# galvo-schematic.net
KiCad netlist of a schematic drawn in EAGLE
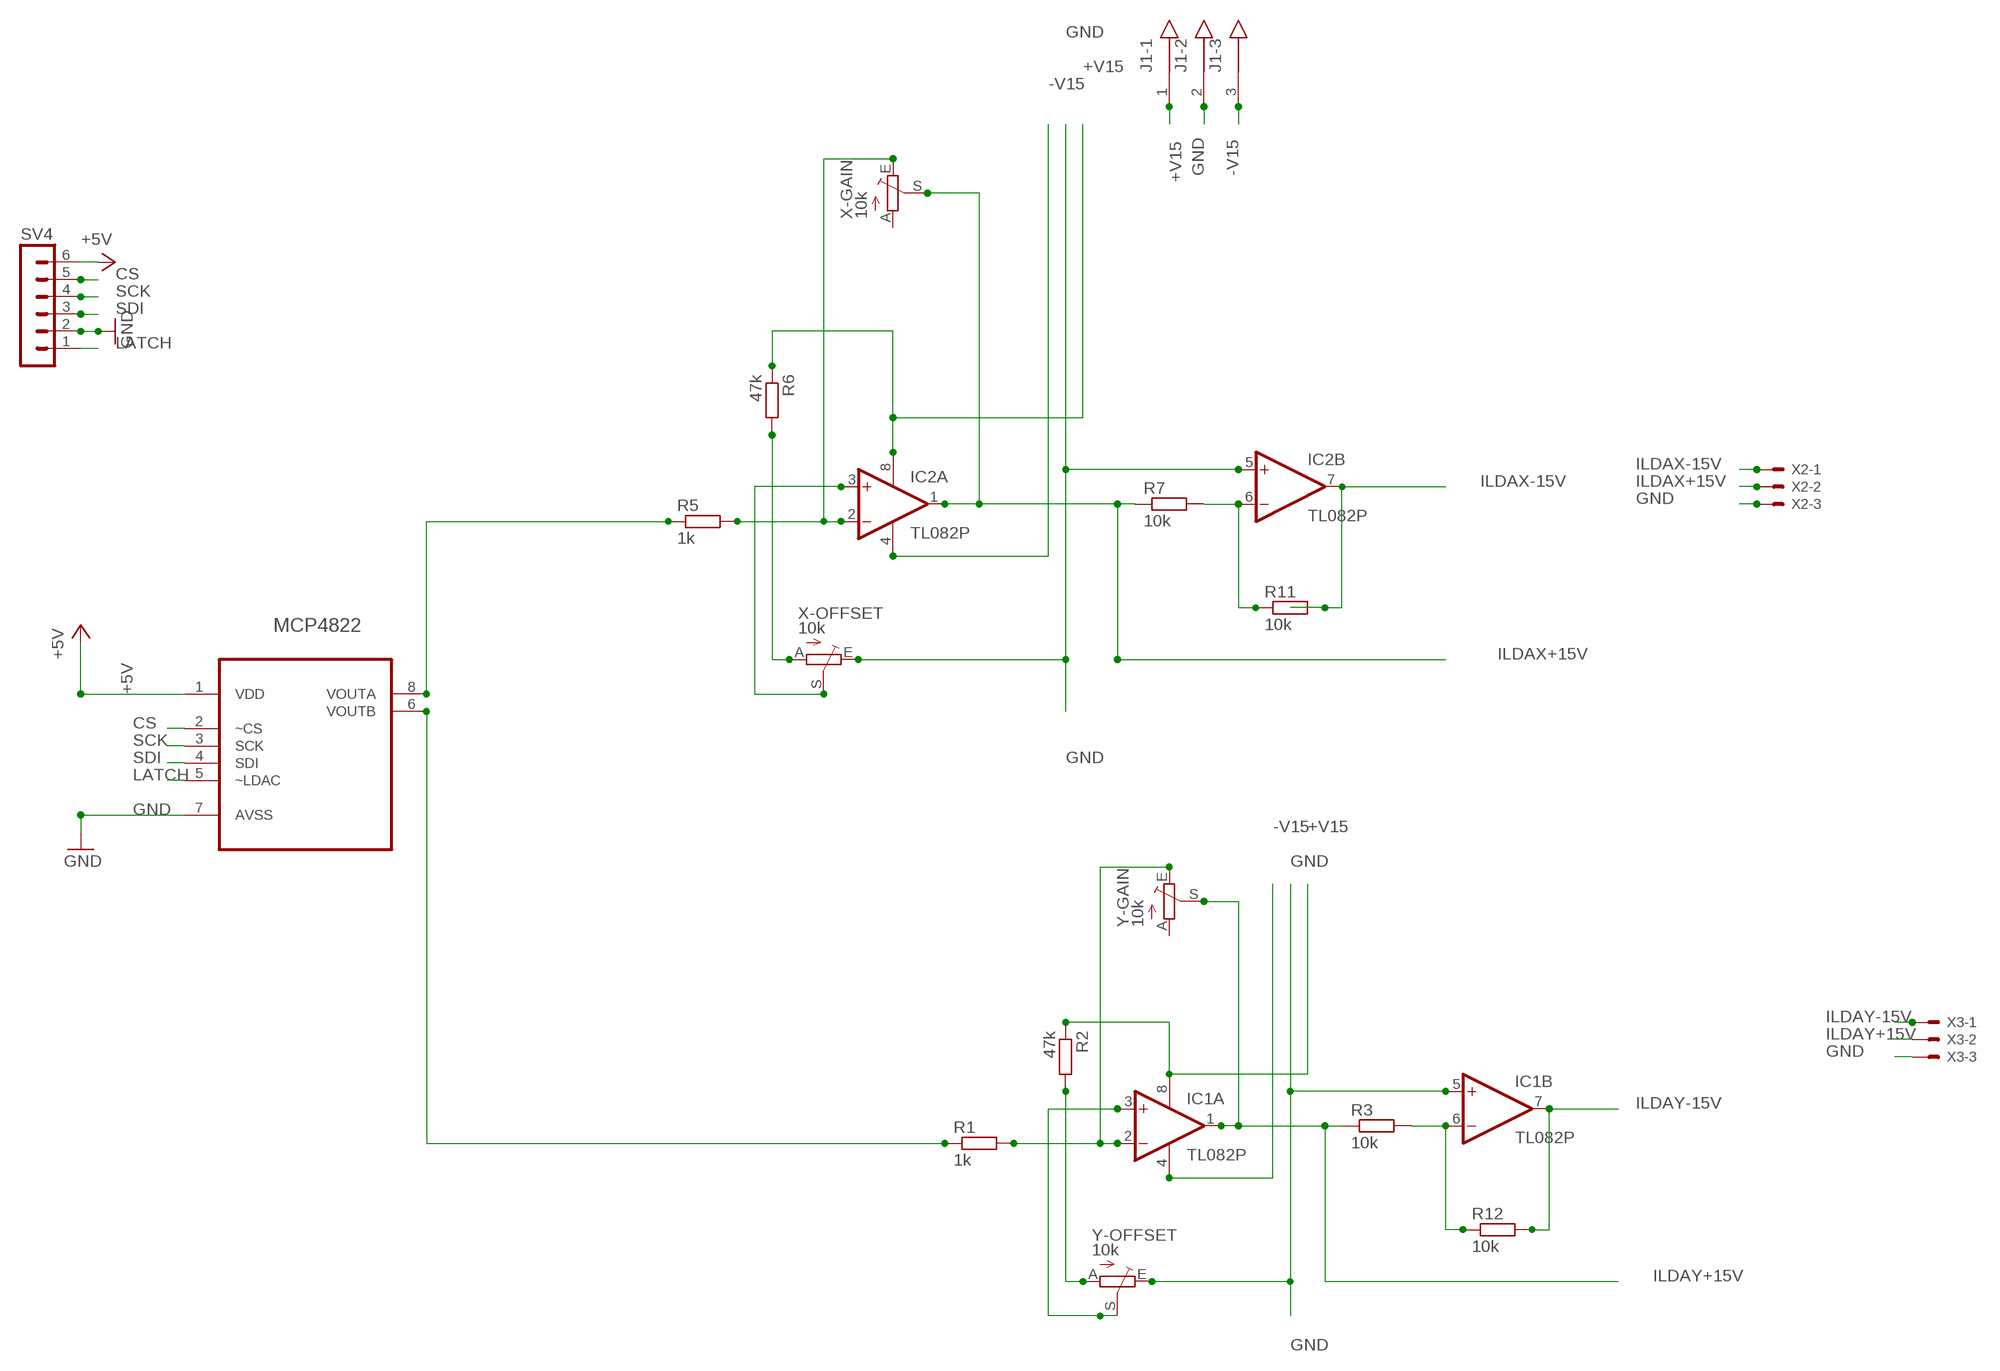
[diagram p0: schematic, sheet 1]

(export (version "E")
  (design (tool "Eeschema 10.0.6"))
  (components
    (comp (ref "IC1")
      (value "TL082P")
      (footprint "eagle-import:DIL08")
      (libsource (lib "eagle-import") (part "TL082P"))
    )
    (comp (ref "IC2")
      (value "TL082P")
      (footprint "eagle-import:DIL08")
      (libsource (lib "eagle-import") (part "TL082P"))
    )
    (comp (ref "J1")
      (value "0022272031")
      (footprint "eagle-import:KK6410-2031_3-PIN")
      (fields (field (name "MANUFACTURER") "Molex Inc"))
      (libsource (lib "eagle-import") (part "0022272031"))
    )
    (comp (ref "MCP4822")
      (value "MCP4822-E/P")
      (footprint "eagle-import:DIP254P762X432-8")
      (libsource (lib "eagle-import") (part "MCP4822-E/P"))
    )
    (comp (ref "R1")
      (value "1k")
      (footprint "eagle-import:0207_10")
      (libsource (lib "eagle-import") (part "R-EU_0207/10"))
    )
    (comp (ref "R2")
      (value "47k")
      (footprint "eagle-import:0207_10")
      (libsource (lib "eagle-import") (part "R-EU_0207/10"))
    )
    (comp (ref "R3")
      (value "10k")
      (footprint "eagle-import:0207_10")
      (libsource (lib "eagle-import") (part "R-EU_0207/10"))
    )
    (comp (ref "R5")
      (value "1k")
      (footprint "eagle-import:0207_10")
      (libsource (lib "eagle-import") (part "R-EU_0207/10"))
    )
    (comp (ref "R6")
      (value "47k")
      (footprint "eagle-import:0207_10")
      (libsource (lib "eagle-import") (part "R-EU_0207/10"))
    )
    (comp (ref "R7")
      (value "10k")
      (footprint "eagle-import:0207_10")
      (libsource (lib "eagle-import") (part "R-EU_0207/10"))
    )
    (comp (ref "R11")
      (value "10k")
      (footprint "eagle-import:0207_10")
      (libsource (lib "eagle-import") (part "R-EU_0207/10"))
    )
    (comp (ref "R12")
      (value "10k")
      (footprint "eagle-import:0207_10")
      (libsource (lib "eagle-import") (part "R-EU_0207/10"))
    )
    (comp (ref "SV4")
      (value "MA06-1")
      (footprint "eagle-import:MA06-1")
      (libsource (lib "eagle-import") (part "MA06-1"))
    )
    (comp (ref "X-GAIN")
      (value "10k")
      (footprint "eagle-import:B25P")
      (libsource (lib "eagle-import") (part "TRIM_EU-B25P"))
    )
    (comp (ref "X-OFFSET")
      (value "10k")
      (footprint "eagle-import:B25P")
      (libsource (lib "eagle-import") (part "TRIM_EU-B25P"))
    )
    (comp (ref "X2")
      (value "JST-XH-03-PIN-ROUND-PAD")
      (footprint "eagle-import:JST-XH-03-PACKAGE-ROUND-PAD")
      (libsource (lib "eagle-import") (part "JST-XH-03-PIN-ROUND-PAD"))
    )
    (comp (ref "X3")
      (value "JST-XH-03-PIN-ROUND-PAD")
      (footprint "eagle-import:JST-XH-03-PACKAGE-ROUND-PAD")
      (libsource (lib "eagle-import") (part "JST-XH-03-PIN-ROUND-PAD"))
    )
    (comp (ref "Y-GAIN")
      (value "10k")
      (footprint "eagle-import:B25P")
      (libsource (lib "eagle-import") (part "TRIM_EU-B25P"))
    )
    (comp (ref "Y-OFFSET")
      (value "10k")
      (footprint "eagle-import:B25P")
      (libsource (lib "eagle-import") (part "TRIM_EU-B25P"))
    )
  )
  (nets
    (net (code "1") (name "+5V") (class "Default")
      (node (ref "MCP4822") (pin "1") (pinfunction "VDD_1") (pintype "power_in"))
      (node (ref "SV4") (pin "6") (pinfunction "6_6") (pintype "passive"))
    )
    (net (code "2") (name "/+V15") (class "Default")
      (node (ref "IC1") (pin "8") (pinfunction "V+_8") (pintype "power_in"))
      (node (ref "IC2") (pin "8") (pinfunction "V+_8") (pintype "power_in"))
      (node (ref "J1") (pin "1") (pinfunction "P$1_1") (pintype "bidirectional"))
      (node (ref "R2") (pin "1") (pinfunction "1_1") (pintype "passive"))
      (node (ref "R6") (pin "1") (pinfunction "1_1") (pintype "passive"))
    )
    (net (code "3") (name "/-V15") (class "Default")
      (node (ref "IC1") (pin "4") (pinfunction "V-_4") (pintype "power_in"))
      (node (ref "IC2") (pin "4") (pinfunction "V-_4") (pintype "power_in"))
      (node (ref "J1") (pin "3") (pinfunction "P$1_3") (pintype "bidirectional"))
    )
    (net (code "4") (name "/CS") (class "Default")
      (node (ref "MCP4822") (pin "2") (pinfunction "~{CS}_2") (pintype "input"))
      (node (ref "SV4") (pin "5") (pinfunction "5_5") (pintype "passive"))
    )
    (net (code "5") (name "/ILDAX+15V") (class "Default")
      (node (ref "IC2") (pin "1") (pinfunction "OUT_1") (pintype "output"))
      (node (ref "R7") (pin "1") (pinfunction "1_1") (pintype "passive"))
      (node (ref "X-GAIN") (pin "S") (pinfunction "S_S") (pintype "passive"))
      (node (ref "X2") (pin "2") (pinfunction "S_2") (pintype "passive"))
    )
    (net (code "6") (name "/ILDAX-15V") (class "Default")
      (node (ref "IC2") (pin "7") (pinfunction "OUT_7") (pintype "output"))
      (node (ref "R11") (pin "2") (pinfunction "2_2") (pintype "passive"))
      (node (ref "X2") (pin "1") (pinfunction "S_1") (pintype "passive"))
    )
    (net (code "7") (name "/ILDAY+15V") (class "Default")
      (node (ref "IC1") (pin "1") (pinfunction "OUT_1") (pintype "output"))
      (node (ref "R3") (pin "1") (pinfunction "1_1") (pintype "passive"))
      (node (ref "X3") (pin "2") (pinfunction "S_2") (pintype "passive"))
      (node (ref "Y-GAIN") (pin "S") (pinfunction "S_S") (pintype "passive"))
    )
    (net (code "8") (name "/ILDAY-15V") (class "Default")
      (node (ref "IC1") (pin "7") (pinfunction "OUT_7") (pintype "output"))
      (node (ref "R12") (pin "2") (pinfunction "2_2") (pintype "passive"))
      (node (ref "X3") (pin "1") (pinfunction "S_1") (pintype "passive"))
    )
    (net (code "9") (name "/LATCH") (class "Default")
      (node (ref "MCP4822") (pin "5") (pinfunction "~{LDAC}_5") (pintype "input"))
      (node (ref "SV4") (pin "1") (pinfunction "1_1") (pintype "passive"))
    )
    (net (code "10") (name "/SCK") (class "Default")
      (node (ref "MCP4822") (pin "3") (pinfunction "SCK_3") (pintype "input"))
      (node (ref "SV4") (pin "4") (pinfunction "4_4") (pintype "passive"))
    )
    (net (code "11") (name "/SDI") (class "Default")
      (node (ref "MCP4822") (pin "4") (pinfunction "SDI_4") (pintype "input"))
      (node (ref "SV4") (pin "3") (pinfunction "3_3") (pintype "passive"))
    )
    (net (code "12") (name "GND") (class "Default")
      (node (ref "IC1") (pin "5") (pinfunction "+IN_5") (pintype "input"))
      (node (ref "IC2") (pin "5") (pinfunction "+IN_5") (pintype "input"))
      (node (ref "J1") (pin "2") (pinfunction "P$1_2") (pintype "bidirectional"))
      (node (ref "MCP4822") (pin "7") (pinfunction "AVSS_7") (pintype "passive"))
      (node (ref "SV4") (pin "2") (pinfunction "2_2") (pintype "passive"))
      (node (ref "X-OFFSET") (pin "E") (pinfunction "E_E") (pintype "passive"))
      (node (ref "X2") (pin "3") (pinfunction "S_3") (pintype "passive"))
      (node (ref "X3") (pin "3") (pinfunction "S_3") (pintype "passive"))
      (node (ref "Y-OFFSET") (pin "E") (pinfunction "E_E") (pintype "passive"))
    )
    (net (code "13") (name "Net-(IC1A-+IN)") (class "Default")
      (node (ref "IC1") (pin "3") (pinfunction "+IN_3") (pintype "input"))
      (node (ref "Y-OFFSET") (pin "S") (pinfunction "S_S") (pintype "passive"))
    )
    (net (code "14") (name "Net-(IC1A--IN)") (class "Default")
      (node (ref "IC1") (pin "2") (pinfunction "-IN_2") (pintype "input"))
      (node (ref "R1") (pin "2") (pinfunction "2_2") (pintype "passive"))
      (node (ref "Y-GAIN") (pin "E") (pinfunction "E_E") (pintype "passive"))
    )
    (net (code "15") (name "Net-(IC1B--IN)") (class "Default")
      (node (ref "IC1") (pin "6") (pinfunction "-IN_6") (pintype "input"))
      (node (ref "R12") (pin "1") (pinfunction "1_1") (pintype "passive"))
      (node (ref "R3") (pin "2") (pinfunction "2_2") (pintype "passive"))
    )
    (net (code "16") (name "Net-(IC2A-+IN)") (class "Default")
      (node (ref "IC2") (pin "3") (pinfunction "+IN_3") (pintype "input"))
      (node (ref "X-OFFSET") (pin "S") (pinfunction "S_S") (pintype "passive"))
    )
    (net (code "17") (name "Net-(IC2A--IN)") (class "Default")
      (node (ref "IC2") (pin "2") (pinfunction "-IN_2") (pintype "input"))
      (node (ref "R5") (pin "2") (pinfunction "2_2") (pintype "passive"))
      (node (ref "X-GAIN") (pin "E") (pinfunction "E_E") (pintype "passive"))
    )
    (net (code "18") (name "Net-(IC2B--IN)") (class "Default")
      (node (ref "IC2") (pin "6") (pinfunction "-IN_6") (pintype "input"))
      (node (ref "R11") (pin "1") (pinfunction "1_1") (pintype "passive"))
      (node (ref "R7") (pin "2") (pinfunction "2_2") (pintype "passive"))
    )
    (net (code "19") (name "Net-(MCP4822-VOUTA)") (class "Default")
      (node (ref "MCP4822") (pin "8") (pinfunction "VOUTA_8") (pintype "output"))
      (node (ref "R5") (pin "1") (pinfunction "1_1") (pintype "passive"))
    )
    (net (code "20") (name "Net-(MCP4822-VOUTB)") (class "Default")
      (node (ref "MCP4822") (pin "6") (pinfunction "VOUTB_6") (pintype "output"))
      (node (ref "R1") (pin "1") (pinfunction "1_1") (pintype "passive"))
    )
    (net (code "21") (name "Net-(R2-Pad2)") (class "Default")
      (node (ref "R2") (pin "2") (pinfunction "2_2") (pintype "passive"))
      (node (ref "Y-OFFSET") (pin "A") (pinfunction "A_A") (pintype "passive"))
    )
    (net (code "22") (name "Net-(R6-Pad2)") (class "Default")
      (node (ref "R6") (pin "2") (pinfunction "2_2") (pintype "passive"))
      (node (ref "X-OFFSET") (pin "A") (pinfunction "A_A") (pintype "passive"))
    )
    (net (code "23") (name "unconnected-(X-GAIN-PadA)") (class "Default")
      (node (ref "X-GAIN") (pin "A") (pinfunction "A_A") (pintype "passive"))
    )
    (net (code "24") (name "unconnected-(Y-GAIN-PadA)") (class "Default")
      (node (ref "Y-GAIN") (pin "A") (pinfunction "A_A") (pintype "passive"))
    )
  )
)
